# Slave_Button.net
KiCad netlist of a schematic drawn in Altium Designer
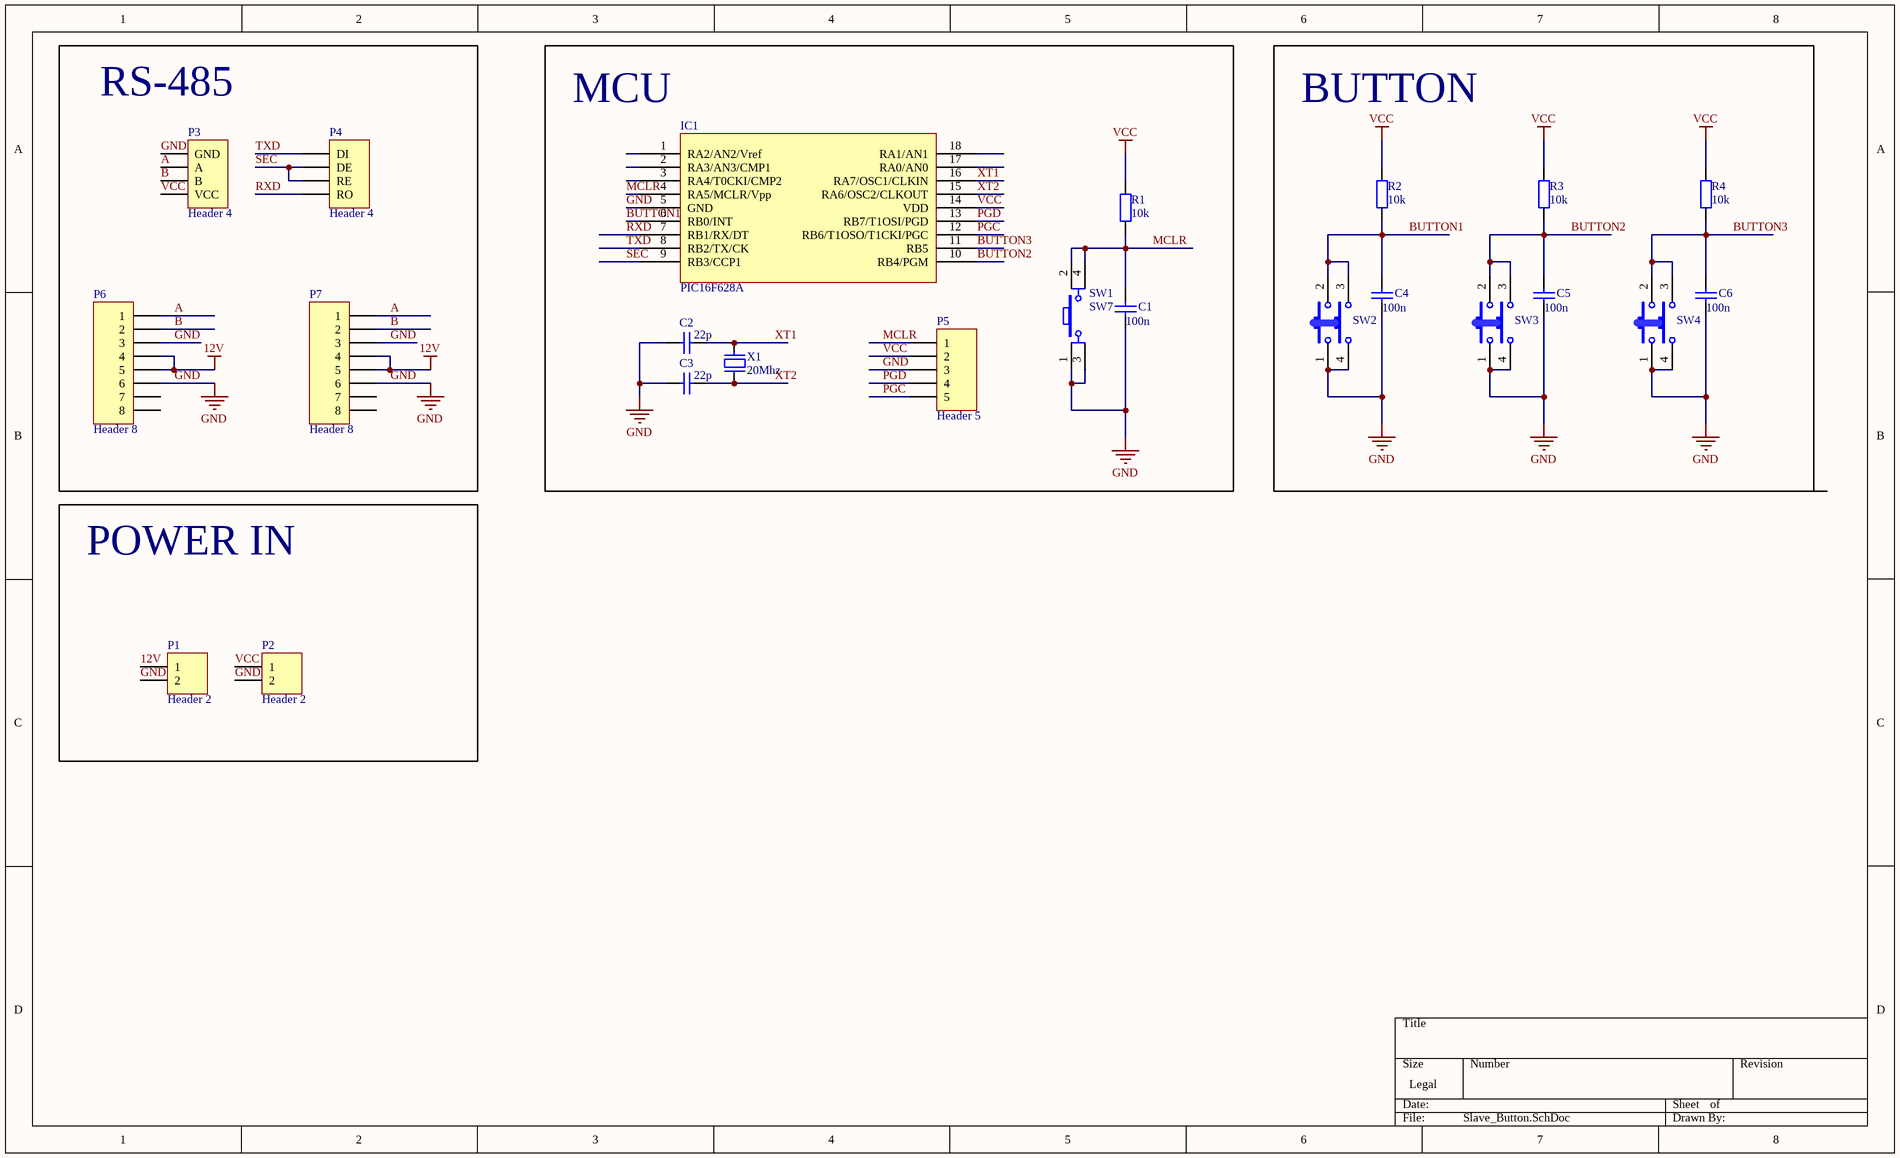
[diagram p0: Slave_Button.SchDoc]

(export (version "E")
  (design (tool "Eeschema 10.0.6"))
  (components
    (comp (ref "C1")
      (value "100n")
      (footprint "Cap Non-Pol 3mm")
      (description "Capacitor")
      (fields (field (name "Comment") "Capacitor Ceramic") (field (name "PUBLISHER") "Altium Limited"))
      (libsource (lib "THG") (part "CapSMD"))
    )
    (comp (ref "C2")
      (value "22p")
      (footprint "Cap Non-Pol 3mm")
      (description "Non-polarized Capacitor")
      (fields (field (name "Comment") "Cap Non-pol") (field (name "PUBLISHER") "Altium Limited"))
      (libsource (lib "THG") (part "Cap Non-pol"))
    )
    (comp (ref "C3")
      (value "22p")
      (footprint "Cap Non-Pol 3mm")
      (description "Non-polarized Capacitor")
      (fields (field (name "Comment") "Cap Non-pol") (field (name "PUBLISHER") "Altium Limited"))
      (libsource (lib "THG") (part "Cap Non-pol"))
    )
    (comp (ref "C4")
      (value "100n")
      (footprint "Cap Non-Pol 3mm")
      (description "Capacitor")
      (fields (field (name "Comment") "Capacitor Ceramic") (field (name "PUBLISHER") "Altium Limited"))
      (libsource (lib "THG") (part "CapSMD"))
    )
    (comp (ref "C5")
      (value "100n")
      (footprint "Cap Non-Pol 3mm")
      (description "Capacitor")
      (fields (field (name "Comment") "Capacitor Ceramic") (field (name "PUBLISHER") "Altium Limited"))
      (libsource (lib "THG") (part "CapSMD"))
    )
    (comp (ref "C6")
      (value "100n")
      (footprint "Cap Non-Pol 3mm")
      (description "Capacitor")
      (fields (field (name "Comment") "Capacitor Ceramic") (field (name "PUBLISHER") "Altium Limited"))
      (libsource (lib "THG") (part "CapSMD"))
    )
    (comp (ref "IC1")
      (value "PIC16F628A")
      (footprint "DIP18/W0.3")
      (libsource (lib "THG") (part "PIC16F628A"))
    )
    (comp (ref "P1")
      (value "Header 2")
      (footprint "HDR1X2")
      (description "Header, 2-Pin")
      (fields (field (name "PUBLISHER") "Altium Limited"))
      (libsource (lib "Miscellaneous Connectors") (part "Header 2"))
    )
    (comp (ref "P2")
      (value "Header 2")
      (footprint "HDR1X2")
      (description "Header, 2-Pin")
      (fields (field (name "PUBLISHER") "Altium Limited"))
      (libsource (lib "Miscellaneous Connectors") (part "Header 2"))
    )
    (comp (ref "P3")
      (value "Header 4")
      (footprint "HDR1X4")
      (description "Header, 4-Pin")
      (fields (field (name "PUBLISHER") "Altium Limited"))
      (libsource (lib "Miscellaneous Connectors") (part "Header 4"))
    )
    (comp (ref "P4")
      (value "Header 4")
      (footprint "HDR1X4")
      (description "Header, 4-Pin")
      (fields (field (name "PUBLISHER") "Altium Limited"))
      (libsource (lib "Miscellaneous Connectors") (part "Header 4"))
    )
    (comp (ref "P5")
      (value "Header 5")
      (footprint "Header 5")
      (description "Header, 5-Pin")
      (fields (field (name "PUBLISHER") "Altium Limited"))
      (libsource (lib "THG") (part "Header 5"))
    )
    (comp (ref "P6")
      (value "Header 8")
      (footprint "RJ11")
      (description "Header, 8-Pin")
      (fields (field (name "PUBLISHER") "Altium Limited"))
      (libsource (lib "THG") (part "Header 8"))
    )
    (comp (ref "P7")
      (value "Header 8")
      (footprint "RJ11")
      (description "Header, 8-Pin")
      (fields (field (name "PUBLISHER") "Altium Limited"))
      (libsource (lib "THG") (part "Header 8"))
    )
    (comp (ref "R1")
      (value "10k")
      (footprint "RESISTOR 1/4W")
      (description "RES_0805")
      (fields (field (name "Comment") "RES_SMD_0805") (field (name "PUBLISHER") "Altium Limited"))
      (libsource (lib "THG") (part "RES_SMD_0805"))
    )
    (comp (ref "R2")
      (value "10k")
      (footprint "RESISTOR 1/4W")
      (description "RES_0805")
      (fields (field (name "Comment") "RES_SMD_0805") (field (name "PUBLISHER") "Altium Limited"))
      (libsource (lib "THG") (part "RES_SMD_0805"))
    )
    (comp (ref "R3")
      (value "10k")
      (footprint "RESISTOR 1/4W")
      (description "RES_0805")
      (fields (field (name "Comment") "RES_SMD_0805") (field (name "PUBLISHER") "Altium Limited"))
      (libsource (lib "THG") (part "RES_SMD_0805"))
    )
    (comp (ref "R4")
      (value "10k")
      (footprint "RESISTOR 1/4W")
      (description "RES_0805")
      (fields (field (name "Comment") "RES_SMD_0805") (field (name "PUBLISHER") "Altium Limited"))
      (libsource (lib "THG") (part "RES_SMD_0805"))
    )
    (comp (ref "SW1")
      (value "SW7")
      (footprint "SW4")
      (description "Switch button 4 pin")
      (libsource (lib "syhaunguyen") (part "SW4"))
    )
    (comp (ref "SW2")
      (value "SW-4P-B")
      (footprint "SW4")
      (description "Switch Big 4 Pin")
      (fields (field (name "PUBLISHER") "Altium Limited"))
      (libsource (lib "hphonglib") (part "SW-4PIN-BIG"))
    )
    (comp (ref "SW3")
      (value "SW-4P-B")
      (footprint "SW4")
      (description "Switch Big 4 Pin")
      (fields (field (name "PUBLISHER") "Altium Limited"))
      (libsource (lib "hphonglib") (part "SW-4PIN-BIG"))
    )
    (comp (ref "SW4")
      (value "SW-4P-B")
      (footprint "SW4")
      (description "Switch Big 4 Pin")
      (fields (field (name "PUBLISHER") "Altium Limited"))
      (libsource (lib "hphonglib") (part "SW-4PIN-BIG"))
    )
    (comp (ref "X1")
      (value "20Mhz")
      (footprint "XT2")
      (description "Crystal For all Crystal 2pin.")
      (libsource (lib "syhaunguyen") (part "XT2"))
    )
  )
  (nets
    (net (code "1") (name "/A") (class "Default")
      (node (ref "P3") (pin "2") (pinfunction "A_2") (pintype "passive"))
      (node (ref "P6") (pin "1") (pinfunction "1_1") (pintype "passive"))
      (node (ref "P7") (pin "1") (pinfunction "1_1") (pintype "passive"))
    )
    (net (code "2") (name "/B") (class "Default")
      (node (ref "P3") (pin "3") (pinfunction "B_3") (pintype "passive"))
      (node (ref "P6") (pin "2") (pinfunction "2_2") (pintype "passive"))
      (node (ref "P7") (pin "2") (pinfunction "2_2") (pintype "passive"))
    )
    (net (code "3") (name "/BUTTON1") (class "Default")
      (node (ref "C4") (pin "2") (pinfunction "2_2") (pintype "passive"))
      (node (ref "IC1") (pin "6") (pinfunction "RB0/INT_6") (pintype "passive"))
      (node (ref "R2") (pin "1") (pinfunction "1_1") (pintype "passive"))
      (node (ref "SW2") (pin "2") (pinfunction "2_2") (pintype "passive"))
      (node (ref "SW2") (pin "3") (pinfunction "3_3") (pintype "passive"))
    )
    (net (code "4") (name "/BUTTON2") (class "Default")
      (node (ref "C5") (pin "2") (pinfunction "2_2") (pintype "passive"))
      (node (ref "IC1") (pin "10") (pinfunction "RB4/PGM_10") (pintype "passive"))
      (node (ref "R3") (pin "1") (pinfunction "1_1") (pintype "passive"))
      (node (ref "SW3") (pin "2") (pinfunction "2_2") (pintype "passive"))
      (node (ref "SW3") (pin "3") (pinfunction "3_3") (pintype "passive"))
    )
    (net (code "5") (name "/BUTTON3") (class "Default")
      (node (ref "C6") (pin "2") (pinfunction "2_2") (pintype "passive"))
      (node (ref "IC1") (pin "11") (pinfunction "RB5_11") (pintype "passive"))
      (node (ref "R4") (pin "1") (pinfunction "1_1") (pintype "passive"))
      (node (ref "SW4") (pin "2") (pinfunction "2_2") (pintype "passive"))
      (node (ref "SW4") (pin "3") (pinfunction "3_3") (pintype "passive"))
    )
    (net (code "6") (name "/MCLR") (class "Default")
      (node (ref "C1") (pin "2") (pinfunction "2_2") (pintype "passive"))
      (node (ref "IC1") (pin "4") (pinfunction "RA5/MCLR/Vpp_4") (pintype "passive"))
      (node (ref "P5") (pin "1") (pinfunction "1_1") (pintype "passive"))
      (node (ref "R1") (pin "1") (pinfunction "1_1") (pintype "passive"))
      (node (ref "SW1") (pin "2") (pintype "passive"))
      (node (ref "SW1") (pin "4") (pintype "passive"))
    )
    (net (code "7") (name "/PGC") (class "Default")
      (node (ref "IC1") (pin "12") (pinfunction "RB6/T1OSO/T1CKI/PGC_12") (pintype "passive"))
      (node (ref "P5") (pin "5") (pinfunction "5_5") (pintype "passive"))
    )
    (net (code "8") (name "/PGD") (class "Default")
      (node (ref "IC1") (pin "13") (pinfunction "RB7/T1OSI/PGD_13") (pintype "passive"))
      (node (ref "P5") (pin "4") (pinfunction "4_4") (pintype "passive"))
    )
    (net (code "9") (name "/RXD") (class "Default")
      (node (ref "IC1") (pin "7") (pinfunction "RB1/RX/DT_7") (pintype "passive"))
      (node (ref "P4") (pin "4") (pinfunction "VCC_4") (pintype "passive"))
    )
    (net (code "10") (name "/SEC") (class "Default")
      (node (ref "IC1") (pin "9") (pinfunction "RB3/CCP1_9") (pintype "passive"))
      (node (ref "P4") (pin "2") (pinfunction "A_2") (pintype "passive"))
      (node (ref "P4") (pin "3") (pinfunction "B_3") (pintype "passive"))
    )
    (net (code "11") (name "/TXD") (class "Default")
      (node (ref "IC1") (pin "8") (pinfunction "RB2/TX/CK_8") (pintype "passive"))
      (node (ref "P4") (pin "1") (pinfunction "GND_1") (pintype "passive"))
    )
    (net (code "12") (name "/XT1") (class "Default")
      (node (ref "C2") (pin "1") (pinfunction "1_1") (pintype "passive"))
      (node (ref "IC1") (pin "16") (pinfunction "RA7/OSC1/CLKIN_16") (pintype "passive"))
      (node (ref "X1") (pin "2") (pinfunction "2_2") (pintype "passive"))
    )
    (net (code "13") (name "/XT2") (class "Default")
      (node (ref "C3") (pin "1") (pinfunction "1_1") (pintype "passive"))
      (node (ref "IC1") (pin "15") (pinfunction "RA6/OSC2/CLKOUT_15") (pintype "passive"))
      (node (ref "X1") (pin "1") (pinfunction "1_1") (pintype "passive"))
    )
    (net (code "14") (name "12V") (class "Default")
      (node (ref "P1") (pin "1") (pinfunction "1_1") (pintype "passive"))
      (node (ref "P6") (pin "4") (pinfunction "4_4") (pintype "passive"))
      (node (ref "P6") (pin "5") (pinfunction "5_5") (pintype "passive"))
      (node (ref "P7") (pin "4") (pinfunction "4_4") (pintype "passive"))
      (node (ref "P7") (pin "5") (pinfunction "5_5") (pintype "passive"))
    )
    (net (code "15") (name "GND") (class "Default")
      (node (ref "C1") (pin "1") (pinfunction "1_1") (pintype "passive"))
      (node (ref "C2") (pin "2") (pinfunction "2_2") (pintype "passive"))
      (node (ref "C3") (pin "2") (pinfunction "2_2") (pintype "passive"))
      (node (ref "C4") (pin "1") (pinfunction "1_1") (pintype "passive"))
      (node (ref "C5") (pin "1") (pinfunction "1_1") (pintype "passive"))
      (node (ref "C6") (pin "1") (pinfunction "1_1") (pintype "passive"))
      (node (ref "IC1") (pin "5") (pinfunction "GND_5") (pintype "passive"))
      (node (ref "P1") (pin "2") (pinfunction "2_2") (pintype "passive"))
      (node (ref "P2") (pin "2") (pinfunction "2_2") (pintype "passive"))
      (node (ref "P3") (pin "1") (pinfunction "GND_1") (pintype "passive"))
      (node (ref "P5") (pin "3") (pinfunction "3_3") (pintype "passive"))
      (node (ref "P6") (pin "3") (pinfunction "3_3") (pintype "passive"))
      (node (ref "P6") (pin "6") (pinfunction "6_6") (pintype "passive"))
      (node (ref "P7") (pin "3") (pinfunction "3_3") (pintype "passive"))
      (node (ref "P7") (pin "6") (pinfunction "6_6") (pintype "passive"))
      (node (ref "SW1") (pin "1") (pintype "passive"))
      (node (ref "SW1") (pin "3") (pintype "passive"))
      (node (ref "SW2") (pin "1") (pinfunction "1_1") (pintype "passive"))
      (node (ref "SW2") (pin "4") (pinfunction "4_4") (pintype "passive"))
      (node (ref "SW3") (pin "1") (pinfunction "1_1") (pintype "passive"))
      (node (ref "SW3") (pin "4") (pinfunction "4_4") (pintype "passive"))
      (node (ref "SW4") (pin "1") (pinfunction "1_1") (pintype "passive"))
      (node (ref "SW4") (pin "4") (pinfunction "4_4") (pintype "passive"))
    )
    (net (code "16") (name "VCC") (class "Default")
      (node (ref "IC1") (pin "14") (pinfunction "VDD_14") (pintype "passive"))
      (node (ref "P2") (pin "1") (pinfunction "1_1") (pintype "passive"))
      (node (ref "P3") (pin "4") (pinfunction "VCC_4") (pintype "passive"))
      (node (ref "P5") (pin "2") (pinfunction "2_2") (pintype "passive"))
      (node (ref "R1") (pin "2") (pinfunction "2_2") (pintype "passive"))
      (node (ref "R2") (pin "2") (pinfunction "2_2") (pintype "passive"))
      (node (ref "R3") (pin "2") (pinfunction "2_2") (pintype "passive"))
      (node (ref "R4") (pin "2") (pinfunction "2_2") (pintype "passive"))
    )
    (net (code "17") (name "unconnected-(IC1-RA0{slash}AN0-Pad17)") (class "Default")
      (node (ref "IC1") (pin "17") (pinfunction "RA0/AN0_17") (pintype "passive"))
    )
    (net (code "18") (name "unconnected-(IC1-RA1{slash}AN1-Pad18)") (class "Default")
      (node (ref "IC1") (pin "18") (pinfunction "RA1/AN1_18") (pintype "passive"))
    )
    (net (code "19") (name "unconnected-(IC1-RA2{slash}AN2{slash}Vref-Pad1)") (class "Default")
      (node (ref "IC1") (pin "1") (pinfunction "RA2/AN2/Vref_1") (pintype "passive"))
    )
    (net (code "20") (name "unconnected-(IC1-RA3{slash}AN3{slash}CMP1-Pad2)") (class "Default")
      (node (ref "IC1") (pin "2") (pinfunction "RA3/AN3/CMP1_2") (pintype "passive"))
    )
    (net (code "21") (name "unconnected-(IC1-RA4{slash}T0CKI{slash}CMP2-Pad3)") (class "Default")
      (node (ref "IC1") (pin "3") (pinfunction "RA4/T0CKI/CMP2_3") (pintype "passive"))
    )
    (net (code "22") (name "unconnected-(P6-Pad7)") (class "Default")
      (node (ref "P6") (pin "7") (pinfunction "7_7") (pintype "passive"))
    )
    (net (code "23") (name "unconnected-(P6-Pad8)") (class "Default")
      (node (ref "P6") (pin "8") (pinfunction "8_8") (pintype "passive"))
    )
    (net (code "24") (name "unconnected-(P7-Pad7)") (class "Default")
      (node (ref "P7") (pin "7") (pinfunction "7_7") (pintype "passive"))
    )
    (net (code "25") (name "unconnected-(P7-Pad8)") (class "Default")
      (node (ref "P7") (pin "8") (pinfunction "8_8") (pintype "passive"))
    )
  )
)
